# Motor_Driver.net
KiCad netlist of a schematic drawn in Altium Designer
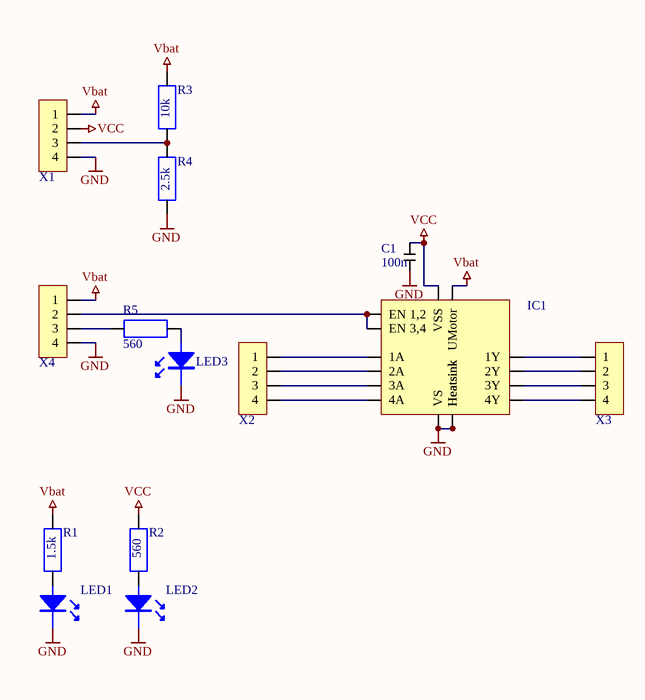
[diagram p0: Motor Driver.SchDoc]

(export (version "E")
  (design (tool "Eeschema 10.0.6"))
  (components
    (comp (ref "C1")
      (value "100n")
      (footprint "0805_R")
      (description "Ceramic Capacitor 0805")
      (libsource (lib "Library") (part "Capacitor 0805"))
    )
    (comp (ref "IC1")
      (value "L293D")
      (footprint "DIP16")
      (description "Motor Driver, 1.2A Output")
      (libsource (lib "Library") (part "L293D"))
    )
    (comp (ref "LED1")
      (value "APT3216CGCK")
      (footprint "LED_3216_GREEN")
      (description "LED SMD green APT3216CGCK")
      (fields (field (name "MANUFACTURER") "Kingbright") (field (name "PART NUMBER") "604-APT3216CGCK"))
      (libsource (lib "Library Smarthome Box") (part "LED"))
    )
    (comp (ref "LED2")
      (value "APT3216CGCK")
      (footprint "LED_3216_GREEN")
      (description "LED SMD green APT3216CGCK")
      (fields (field (name "MANUFACTURER") "Kingbright") (field (name "PART NUMBER") "604-APT3216CGCK"))
      (libsource (lib "Library Smarthome Box") (part "LED"))
    )
    (comp (ref "LED3")
      (value "APT3216CGCK")
      (footprint "LED_3216_GREEN")
      (description "LED SMD green APT3216CGCK")
      (fields (field (name "MANUFACTURER") "Kingbright") (field (name "PART NUMBER") "604-APT3216CGCK"))
      (libsource (lib "Library Smarthome Box") (part "LED"))
    )
    (comp (ref "R1")
      (value "Chip Resistor 10k, 0805, 1%")
      (footprint "0805_R")
      (description "Resistor 10k 0.125W 0805")
      (fields
        (field (name "MANUFACTURER") "Vishay")
        (field (name "PART NUMBER") "CRCW080510K0FKEAC")
        (field (name "COMMENT_1") "1.5k")
      )
      (libsource (lib "Library Smarthome Box") (part "RESISTOR"))
    )
    (comp (ref "R2")
      (value "Chip Resistor 10k, 0805, 1%")
      (footprint "0805_R")
      (description "Resistor 10k 0.125W 0805")
      (fields
        (field (name "MANUFACTURER") "Vishay")
        (field (name "PART NUMBER") "CRCW080510K0FKEAC")
        (field (name "COMMENT_1") "560")
      )
      (libsource (lib "Library Smarthome Box") (part "RESISTOR"))
    )
    (comp (ref "R3")
      (value "Chip Resistor 10k, 0805, 1%")
      (footprint "0805_R")
      (description "Resistor 10k 0.125W 0805")
      (fields
        (field (name "MANUFACTURER") "Vishay")
        (field (name "PART NUMBER") "CRCW080510K0FKEAC")
        (field (name "COMMENT_1") "10k")
      )
      (libsource (lib "Library Smarthome Box") (part "RESISTOR"))
    )
    (comp (ref "R4")
      (value "Chip Resistor 10k, 0805, 1%")
      (footprint "0805_R")
      (description "Resistor 10k 0.125W 0805")
      (fields
        (field (name "MANUFACTURER") "Vishay")
        (field (name "PART NUMBER") "CRCW080510K0FKEAC")
        (field (name "COMMENT_1") "2.5k")
      )
      (libsource (lib "Library Smarthome Box") (part "RESISTOR"))
    )
    (comp (ref "R5")
      (value "Chip Resistor 10k, 0805, 1%")
      (footprint "0805_R")
      (description "Resistor 10k 0.125W 0805")
      (fields
        (field (name "MANUFACTURER") "Vishay")
        (field (name "PART NUMBER") "CRCW080510K0FKEAC")
        (field (name "COMMENT_1") "560")
      )
      (libsource (lib "Library Smarthome Box") (part "RESISTOR"))
    )
    (comp (ref "X1")
      (value "Pin Header 4x1 2.54mm")
      (footprint "PTSM 0,5 4-2,5-H SMD")
      (description "PTSM 4 Pol")
      (fields (field (name "MANUFACTURER") "Phoenix Contacdt") (field (name "PART NUMBER") "1814650"))
      (libsource (lib "") (part "PTSM 0,5/ 4-2,5-H SMD_1"))
    )
    (comp (ref "X2")
      (value "Pin Header 4x1 2.54mm")
      (footprint "PTSM 0,5 4-2,5-H SMD")
      (description "PTSM 4 Pol")
      (fields (field (name "MANUFACTURER") "Phoenix Contacdt") (field (name "PART NUMBER") "1814650"))
      (libsource (lib "") (part "PTSM 0,5/ 4-2,5-H SMD_1"))
    )
    (comp (ref "X3")
      (value "Pin Header 4x1 2.54mm")
      (footprint "PTSM 0,5 4-2,5-H SMD")
      (description "PTSM 4 Pol")
      (fields (field (name "MANUFACTURER") "Phoenix Contacdt") (field (name "PART NUMBER") "1814650"))
      (libsource (lib "Library") (part "PTSM 0,5/ 4-2,5-H SMD"))
    )
    (comp (ref "X4")
      (value "Pin Header 4x1 2.54mm")
      (footprint "PTSM 0,5 4-2,5-H SMD")
      (description "PTSM 4 Pol")
      (fields (field (name "MANUFACTURER") "Phoenix Contacdt") (field (name "PART NUMBER") "1814650"))
      (libsource (lib "") (part "PTSM 0,5/ 4-2,5-H SMD_1"))
    )
  )
  (nets
    (net (code "1") (name "GND") (class "Default")
      (node (ref "C1") (pin "1") (pinfunction "1_1") (pintype "passive"))
      (node (ref "IC1") (pin "12") (pinfunction "Heatsink_12") (pintype "passive"))
      (node (ref "IC1") (pin "13") (pinfunction "Heatsink_13") (pintype "passive"))
      (node (ref "IC1") (pin "4") (pinfunction "Heatsink_4") (pintype "passive"))
      (node (ref "IC1") (pin "5") (pinfunction "Heatsink_5") (pintype "passive"))
      (node (ref "IC1") (pin "8") (pinfunction "VS_8") (pintype "passive"))
      (node (ref "LED1") (pin "K") (pinfunction "2_K") (pintype "passive"))
      (node (ref "LED2") (pin "K") (pinfunction "2_K") (pintype "passive"))
      (node (ref "LED3") (pin "K") (pinfunction "2_K") (pintype "passive"))
      (node (ref "R4") (pin "1") (pintype "passive"))
      (node (ref "X1") (pin "4") (pinfunction "4_4") (pintype "passive"))
      (node (ref "X4") (pin "4") (pinfunction "4_4") (pintype "passive"))
    )
    (net (code "2") (name "Net-(IC1-1A)") (class "Default")
      (node (ref "IC1") (pin "2") (pinfunction "1A_2") (pintype "passive"))
      (node (ref "X2") (pin "1") (pinfunction "1_1") (pintype "passive"))
    )
    (net (code "3") (name "Net-(IC1-1Y)") (class "Default")
      (node (ref "IC1") (pin "3") (pinfunction "1Y_3") (pintype "passive"))
      (node (ref "X3") (pin "1") (pinfunction "1_1") (pintype "passive"))
    )
    (net (code "4") (name "Net-(IC1-2A)") (class "Default")
      (node (ref "IC1") (pin "7") (pinfunction "2A_7") (pintype "passive"))
      (node (ref "X2") (pin "2") (pinfunction "2_2") (pintype "passive"))
    )
    (net (code "5") (name "Net-(IC1-2Y)") (class "Default")
      (node (ref "IC1") (pin "6") (pinfunction "2Y_6") (pintype "passive"))
      (node (ref "X3") (pin "2") (pinfunction "2_2") (pintype "passive"))
    )
    (net (code "6") (name "Net-(IC1-3A)") (class "Default")
      (node (ref "IC1") (pin "10") (pinfunction "3A_10") (pintype "passive"))
      (node (ref "X2") (pin "3") (pinfunction "3_3") (pintype "passive"))
    )
    (net (code "7") (name "Net-(IC1-3Y)") (class "Default")
      (node (ref "IC1") (pin "11") (pinfunction "3Y_11") (pintype "passive"))
      (node (ref "X3") (pin "3") (pinfunction "3_3") (pintype "passive"))
    )
    (net (code "8") (name "Net-(IC1-4A)") (class "Default")
      (node (ref "IC1") (pin "15") (pinfunction "4A_15") (pintype "passive"))
      (node (ref "X2") (pin "4") (pinfunction "4_4") (pintype "passive"))
    )
    (net (code "9") (name "Net-(IC1-4Y)") (class "Default")
      (node (ref "IC1") (pin "14") (pinfunction "4Y_14") (pintype "passive"))
      (node (ref "X3") (pin "4") (pinfunction "4_4") (pintype "passive"))
    )
    (net (code "10") (name "Net-(IC1-EN_1,2)") (class "Default")
      (node (ref "IC1") (pin "1") (pinfunction "EN_1,2_1") (pintype "passive"))
      (node (ref "IC1") (pin "9") (pinfunction "EN_3,4_9") (pintype "passive"))
      (node (ref "X4") (pin "2") (pinfunction "2_2") (pintype "passive"))
    )
    (net (code "11") (name "Net-(LED1-1)") (class "Default")
      (node (ref "LED1") (pin "A") (pinfunction "1_A") (pintype "passive"))
      (node (ref "R1") (pin "1") (pintype "passive"))
    )
    (net (code "12") (name "Net-(LED2-1)") (class "Default")
      (node (ref "LED2") (pin "A") (pinfunction "1_A") (pintype "passive"))
      (node (ref "R2") (pin "1") (pintype "passive"))
    )
    (net (code "13") (name "Net-(LED3-1)") (class "Default")
      (node (ref "LED3") (pin "A") (pinfunction "1_A") (pintype "passive"))
      (node (ref "R5") (pin "2") (pintype "passive"))
    )
    (net (code "14") (name "Net-(R3-Pad1)") (class "Default")
      (node (ref "R3") (pin "1") (pintype "passive"))
      (node (ref "R4") (pin "2") (pintype "passive"))
      (node (ref "X1") (pin "3") (pinfunction "3_3") (pintype "passive"))
    )
    (net (code "15") (name "Net-(R5-Pad1)") (class "Default")
      (node (ref "R5") (pin "1") (pintype "passive"))
      (node (ref "X4") (pin "3") (pinfunction "3_3") (pintype "passive"))
    )
    (net (code "16") (name "VCC") (class "Default")
      (node (ref "C1") (pin "2") (pinfunction "2_2") (pintype "passive"))
      (node (ref "IC1") (pin "16") (pinfunction "VSS_16") (pintype "passive"))
      (node (ref "R2") (pin "2") (pintype "passive"))
      (node (ref "X1") (pin "2") (pinfunction "2_2") (pintype "passive"))
    )
    (net (code "17") (name "Vbat") (class "Default")
      (node (ref "IC1") (pin "10") (pinfunction "UMotor_10") (pintype "passive"))
      (node (ref "R1") (pin "2") (pintype "passive"))
      (node (ref "R3") (pin "2") (pintype "passive"))
      (node (ref "X1") (pin "1") (pinfunction "1_1") (pintype "passive"))
      (node (ref "X4") (pin "1") (pinfunction "1_1") (pintype "passive"))
    )
  )
)
